# Schematic_CNC.net
KiCad netlist of a schematic drawn in Altium Designer
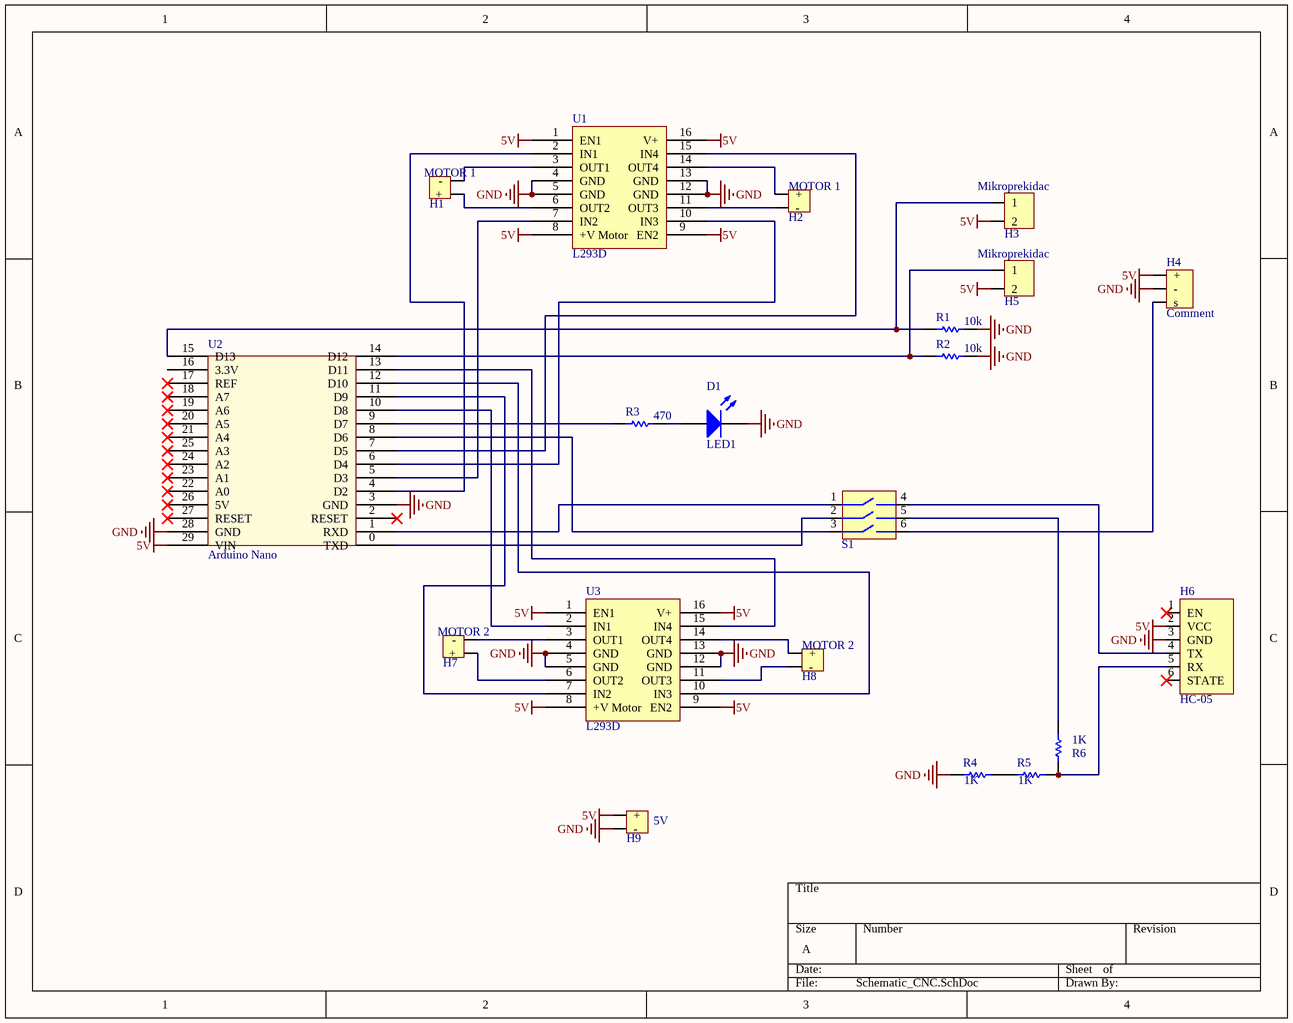
[diagram p0: Schematic_CNC.SchDoc]

(export (version "E")
  (design (tool "Eeschema 10.0.6"))
  (components
    (comp (ref "D1")
      (value "LED1")
      (footprint "LED-1")
      (description "Typical RED GaAs LED")
      (fields (field (name "PUBLISHER") "Altium Limited"))
      (libsource (lib "Miscellaneous Devices") (part "LED1"))
    )
    (comp (ref "H1")
      (value "MOTOR 1")
      (footprint "1x2 plavi sraf")
      (libsource (lib "Konektori") (part "1x2 plavi sraf"))
    )
    (comp (ref "H2")
      (value "MOTOR 1")
      (footprint "1x2 plavi sraf")
      (libsource (lib "") (part "1x2 plavi sraf_1"))
    )
    (comp (ref "H3")
      (value "Mikroprekidac")
      (footprint "1X2 HEADER")
      (libsource (lib "Konektori") (part "1X2 HEADER"))
    )
    (comp (ref "H4")
      (value "Comment")
      (footprint "1x3 plavi sraf")
      (libsource (lib "Konektori") (part "1x3 plavi sraf"))
    )
    (comp (ref "H5")
      (value "Mikroprekidac")
      (footprint "1X2 HEADER")
      (libsource (lib "Konektori") (part "1X2 HEADER"))
    )
    (comp (ref "H6") (value "HC-05") (footprint "HC-05") (libsource (lib "Bluetooth") (part "HC-05")))
    (comp (ref "H7")
      (value "MOTOR 2")
      (footprint "1x2 plavi sraf")
      (libsource (lib "Konektori") (part "1x2 plavi sraf"))
    )
    (comp (ref "H8")
      (value "MOTOR 2")
      (footprint "1x2 plavi sraf")
      (libsource (lib "") (part "1x2 plavi sraf_1"))
    )
    (comp (ref "H9") (value "5V") (footprint "1x2 plavi sraf") (libsource (lib "") (part "1x2 plavi sraf_1")))
    (comp (ref "R1")
      (value "10k")
      (footprint "AXIAL-0.3")
      (description "Resistor")
      (fields (field (name "Comment") "Res1") (field (name "PUBLISHER") "Altium Limited"))
      (libsource (lib "Miscellaneous Devices") (part "Res1"))
    )
    (comp (ref "R2")
      (value "10k")
      (footprint "AXIAL-0.3")
      (description "Resistor")
      (fields (field (name "Comment") "Res1") (field (name "PUBLISHER") "Altium Limited"))
      (libsource (lib "Miscellaneous Devices") (part "Res1"))
    )
    (comp (ref "R3")
      (value "470")
      (footprint "AXIAL-0.3")
      (description "Resistor")
      (fields (field (name "Comment") "Res1") (field (name "PUBLISHER") "Altium Limited"))
      (libsource (lib "Miscellaneous Devices") (part "Res1"))
    )
    (comp (ref "R4")
      (value "1K")
      (footprint "AXIAL-0.3")
      (description "Resistor")
      (fields (field (name "Comment") "Res1") (field (name "PUBLISHER") "Altium Limited"))
      (libsource (lib "Miscellaneous Devices") (part "Res1"))
    )
    (comp (ref "R5")
      (value "1K")
      (footprint "AXIAL-0.3")
      (description "Resistor")
      (fields (field (name "Comment") "Res1") (field (name "PUBLISHER") "Altium Limited"))
      (libsource (lib "Miscellaneous Devices") (part "Res1"))
    )
    (comp (ref "R6")
      (value "1K")
      (footprint "AXIAL-0.3")
      (description "Resistor")
      (fields (field (name "Comment") "Res1") (field (name "PUBLISHER") "Altium Limited"))
      (libsource (lib "Miscellaneous Devices") (part "Res1"))
    )
    (comp (ref "S1")
      (value "3X DIP Switch")
      (footprint "3X DIP SWITCH")
      (libsource (lib "Konektori") (part "3X DIP Switch"))
    )
    (comp (ref "U1")
      (value "L293D")
      (footprint "L293D")
      (description "Motor Driver")
      (libsource (lib "Motor Drivers") (part "L293D"))
    )
    (comp (ref "U2")
      (value "Arduino Nano")
      (footprint "Arduino nano")
      (libsource (lib "Arduino") (part "ArduinoNano"))
    )
    (comp (ref "U3")
      (value "L293D")
      (footprint "L293D")
      (description "Motor Driver")
      (libsource (lib "Motor Drivers") (part "L293D"))
    )
  )
  (nets
    (net (code "1") (name "5V") (class "Default")
      (node (ref "H3") (pin "2") (pinfunction "2_2") (pintype "passive"))
      (node (ref "H4") (pin "1") (pinfunction "+_1") (pintype "passive"))
      (node (ref "H5") (pin "2") (pinfunction "2_2") (pintype "passive"))
      (node (ref "H6") (pin "2") (pinfunction "VCC_2") (pintype "passive"))
      (node (ref "H9") (pin "1") (pinfunction "+_1") (pintype "passive"))
      (node (ref "U1") (pin "1") (pinfunction "EN1_1") (pintype "passive"))
      (node (ref "U1") (pin "16") (pinfunction "V+_16") (pintype "passive"))
      (node (ref "U1") (pin "8") (pinfunction "+V_Motor_8") (pintype "passive"))
      (node (ref "U1") (pin "9") (pinfunction "EN2_9") (pintype "passive"))
      (node (ref "U2") (pin "29") (pinfunction "VIN_29") (pintype "passive"))
      (node (ref "U3") (pin "1") (pinfunction "EN1_1") (pintype "passive"))
      (node (ref "U3") (pin "16") (pinfunction "V+_16") (pintype "passive"))
      (node (ref "U3") (pin "8") (pinfunction "+V_Motor_8") (pintype "passive"))
      (node (ref "U3") (pin "9") (pinfunction "EN2_9") (pintype "passive"))
    )
    (net (code "2") (name "GND") (class "Default")
      (node (ref "D1") (pin "2") (pinfunction "K_2") (pintype "passive"))
      (node (ref "H4") (pin "2") (pinfunction "-_2") (pintype "passive"))
      (node (ref "H6") (pin "3") (pinfunction "GND_3") (pintype "passive"))
      (node (ref "H9") (pin "2") (pinfunction "-_2") (pintype "passive"))
      (node (ref "R1") (pin "2") (pinfunction "2_2") (pintype "passive"))
      (node (ref "R2") (pin "2") (pinfunction "2_2") (pintype "passive"))
      (node (ref "R4") (pin "1") (pinfunction "1_1") (pintype "passive"))
      (node (ref "U1") (pin "12") (pinfunction "GND_12") (pintype "passive"))
      (node (ref "U1") (pin "13") (pinfunction "GND_13") (pintype "passive"))
      (node (ref "U1") (pin "4") (pinfunction "GND_4") (pintype "passive"))
      (node (ref "U1") (pin "5") (pinfunction "GND_5") (pintype "passive"))
      (node (ref "U2") (pin "28") (pinfunction "GND_28") (pintype "passive"))
      (node (ref "U2") (pin "3") (pinfunction "GND_3") (pintype "passive"))
      (node (ref "U3") (pin "12") (pinfunction "GND_12") (pintype "passive"))
      (node (ref "U3") (pin "13") (pinfunction "GND_13") (pintype "passive"))
      (node (ref "U3") (pin "4") (pinfunction "GND_4") (pintype "passive"))
      (node (ref "U3") (pin "5") (pinfunction "GND_5") (pintype "passive"))
    )
    (net (code "3") (name "Net-(D1-A)") (class "Default")
      (node (ref "D1") (pin "1") (pinfunction "A_1") (pintype "passive"))
      (node (ref "R3") (pin "2") (pinfunction "2_2") (pintype "passive"))
    )
    (net (code "4") (name "Net-(H1-+)") (class "Default")
      (node (ref "H1") (pin "1") (pinfunction "+_1") (pintype "passive"))
      (node (ref "U1") (pin "6") (pinfunction "OUT2_6") (pintype "passive"))
    )
    (net (code "5") (name "Net-(H1--)") (class "Default")
      (node (ref "H1") (pin "2") (pinfunction "-_2") (pintype "passive"))
      (node (ref "U1") (pin "3") (pinfunction "OUT1_3") (pintype "passive"))
    )
    (net (code "6") (name "Net-(H2-+)") (class "Default")
      (node (ref "H2") (pin "1") (pinfunction "+_1") (pintype "passive"))
      (node (ref "U1") (pin "14") (pinfunction "OUT4_14") (pintype "passive"))
    )
    (net (code "7") (name "Net-(H2--)") (class "Default")
      (node (ref "H2") (pin "2") (pinfunction "-_2") (pintype "passive"))
      (node (ref "U1") (pin "11") (pinfunction "OUT3_11") (pintype "passive"))
    )
    (net (code "8") (name "Net-(H4-s)") (class "Default")
      (node (ref "H4") (pin "3") (pinfunction "s_3") (pintype "passive"))
      (node (ref "S1") (pin "6") (pinfunction "6_6") (pintype "passive"))
    )
    (net (code "9") (name "Net-(H6-RX)") (class "Default")
      (node (ref "H6") (pin "5") (pinfunction "RX_5") (pintype "passive"))
      (node (ref "R5") (pin "2") (pinfunction "2_2") (pintype "passive"))
      (node (ref "R6") (pin "2") (pinfunction "2_2") (pintype "passive"))
    )
    (net (code "10") (name "Net-(H6-TX)") (class "Default")
      (node (ref "H6") (pin "4") (pinfunction "TX_4") (pintype "passive"))
      (node (ref "S1") (pin "4") (pinfunction "4_4") (pintype "passive"))
    )
    (net (code "11") (name "Net-(H7-+)") (class "Default")
      (node (ref "H7") (pin "1") (pinfunction "+_1") (pintype "passive"))
      (node (ref "U3") (pin "6") (pinfunction "OUT2_6") (pintype "passive"))
    )
    (net (code "12") (name "Net-(H7--)") (class "Default")
      (node (ref "H7") (pin "2") (pinfunction "-_2") (pintype "passive"))
      (node (ref "U3") (pin "3") (pinfunction "OUT1_3") (pintype "passive"))
    )
    (net (code "13") (name "Net-(H8-+)") (class "Default")
      (node (ref "H8") (pin "1") (pinfunction "+_1") (pintype "passive"))
      (node (ref "U3") (pin "14") (pinfunction "OUT4_14") (pintype "passive"))
    )
    (net (code "14") (name "Net-(H8--)") (class "Default")
      (node (ref "H8") (pin "2") (pinfunction "-_2") (pintype "passive"))
      (node (ref "U3") (pin "11") (pinfunction "OUT3_11") (pintype "passive"))
    )
    (net (code "15") (name "Net-(R4-Pad2)") (class "Default")
      (node (ref "R4") (pin "2") (pinfunction "2_2") (pintype "passive"))
      (node (ref "R5") (pin "1") (pinfunction "1_1") (pintype "passive"))
    )
    (net (code "16") (name "Net-(R6-Pad1)") (class "Default")
      (node (ref "R6") (pin "1") (pinfunction "1_1") (pintype "passive"))
      (node (ref "S1") (pin "5") (pinfunction "5_5") (pintype "passive"))
    )
    (net (code "17") (name "Net-(U1-IN1)") (class "Default")
      (node (ref "U1") (pin "2") (pinfunction "IN1_2") (pintype "passive"))
      (node (ref "U2") (pin "4") (pinfunction "D2_4") (pintype "passive"))
    )
    (net (code "18") (name "Net-(U1-IN2)") (class "Default")
      (node (ref "U1") (pin "7") (pinfunction "IN2_7") (pintype "passive"))
      (node (ref "U2") (pin "5") (pinfunction "D3_5") (pintype "passive"))
    )
    (net (code "19") (name "Net-(U1-IN3)") (class "Default")
      (node (ref "U1") (pin "10") (pinfunction "IN3_10") (pintype "passive"))
      (node (ref "U2") (pin "6") (pinfunction "D4_6") (pintype "passive"))
    )
    (net (code "20") (name "Net-(U1-IN4)") (class "Default")
      (node (ref "U1") (pin "15") (pinfunction "IN4_15") (pintype "passive"))
      (node (ref "U2") (pin "7") (pinfunction "D5_7") (pintype "passive"))
    )
    (net (code "21") (name "Net-(U2-D6)") (class "Default")
      (node (ref "S1") (pin "3") (pinfunction "3_3") (pintype "passive"))
      (node (ref "U2") (pin "8") (pinfunction "D6_8") (pintype "passive"))
    )
    (net (code "22") (name "Net-(U2-D7)") (class "Default")
      (node (ref "R3") (pin "1") (pinfunction "1_1") (pintype "passive"))
      (node (ref "U2") (pin "9") (pinfunction "D7_9") (pintype "passive"))
    )
    (net (code "23") (name "Net-(U2-D8)") (class "Default")
      (node (ref "U2") (pin "10") (pinfunction "D8_10") (pintype "passive"))
      (node (ref "U3") (pin "2") (pinfunction "IN1_2") (pintype "passive"))
    )
    (net (code "24") (name "Net-(U2-D9)") (class "Default")
      (node (ref "U2") (pin "11") (pinfunction "D9_11") (pintype "passive"))
      (node (ref "U3") (pin "7") (pinfunction "IN2_7") (pintype "passive"))
    )
    (net (code "25") (name "Net-(U2-D10)") (class "Default")
      (node (ref "U2") (pin "12") (pinfunction "D10_12") (pintype "passive"))
      (node (ref "U3") (pin "10") (pinfunction "IN3_10") (pintype "passive"))
    )
    (net (code "26") (name "Net-(U2-D11)") (class "Default")
      (node (ref "U2") (pin "13") (pinfunction "D11_13") (pintype "passive"))
      (node (ref "U3") (pin "15") (pinfunction "IN4_15") (pintype "passive"))
    )
    (net (code "27") (name "Net-(U2-D12)") (class "Default")
      (node (ref "H5") (pin "1") (pinfunction "1_1") (pintype "passive"))
      (node (ref "R2") (pin "1") (pinfunction "1_1") (pintype "passive"))
      (node (ref "U2") (pin "14") (pinfunction "D12_14") (pintype "passive"))
    )
    (net (code "28") (name "Net-(U2-D13)") (class "Default")
      (node (ref "H3") (pin "1") (pinfunction "1_1") (pintype "passive"))
      (node (ref "R1") (pin "1") (pinfunction "1_1") (pintype "passive"))
      (node (ref "U2") (pin "15") (pinfunction "D13_15") (pintype "passive"))
    )
    (net (code "29") (name "Net-(U2-RXD)") (class "Default")
      (node (ref "S1") (pin "1") (pinfunction "1_1") (pintype "passive"))
      (node (ref "U2") (pin "1") (pinfunction "RXD_1") (pintype "passive"))
    )
    (net (code "30") (name "Net-(U2-TXD)") (class "Default")
      (node (ref "S1") (pin "2") (pinfunction "2_2") (pintype "passive"))
      (node (ref "U2") (pin "0") (pinfunction "TXD_0") (pintype "passive"))
    )
    (net (code "31") (name "unconnected-(H6-EN-Pad1)") (class "Default")
      (node (ref "H6") (pin "1") (pinfunction "EN_1") (pintype "passive+no_connect"))
    )
    (net (code "32") (name "unconnected-(H6-STATE-Pad6)") (class "Default")
      (node (ref "H6") (pin "6") (pinfunction "STATE_6") (pintype "passive+no_connect"))
    )
    (net (code "33") (name "unconnected-(U2-3.3V-Pad16)") (class "Default")
      (node (ref "U2") (pin "16") (pinfunction "3.3V_16") (pintype "passive"))
    )
    (net (code "34") (name "unconnected-(U2-5V-Pad26)") (class "Default")
      (node (ref "U2") (pin "26") (pinfunction "5V_26") (pintype "passive+no_connect"))
    )
    (net (code "35") (name "unconnected-(U2-A0-Pad22)") (class "Default")
      (node (ref "U2") (pin "22") (pinfunction "A0_22") (pintype "passive+no_connect"))
    )
    (net (code "36") (name "unconnected-(U2-A1-Pad23)") (class "Default")
      (node (ref "U2") (pin "23") (pinfunction "A1_23") (pintype "passive+no_connect"))
    )
    (net (code "37") (name "unconnected-(U2-A2-Pad24)") (class "Default")
      (node (ref "U2") (pin "24") (pinfunction "A2_24") (pintype "passive+no_connect"))
    )
    (net (code "38") (name "unconnected-(U2-A3-Pad25)") (class "Default")
      (node (ref "U2") (pin "25") (pinfunction "A3_25") (pintype "passive+no_connect"))
    )
    (net (code "39") (name "unconnected-(U2-A4-Pad21)") (class "Default")
      (node (ref "U2") (pin "21") (pinfunction "A4_21") (pintype "passive+no_connect"))
    )
    (net (code "40") (name "unconnected-(U2-A5-Pad20)") (class "Default")
      (node (ref "U2") (pin "20") (pinfunction "A5_20") (pintype "passive+no_connect"))
    )
    (net (code "41") (name "unconnected-(U2-A6-Pad19)") (class "Default")
      (node (ref "U2") (pin "19") (pinfunction "A6_19") (pintype "passive+no_connect"))
    )
    (net (code "42") (name "unconnected-(U2-A7-Pad18)") (class "Default")
      (node (ref "U2") (pin "18") (pinfunction "A7_18") (pintype "passive+no_connect"))
    )
    (net (code "43") (name "unconnected-(U2-REF-Pad17)") (class "Default")
      (node (ref "U2") (pin "17") (pinfunction "REF_17") (pintype "passive+no_connect"))
    )
    (net (code "44") (name "unconnected-(U2-RESET-Pad2)") (class "Default")
      (node (ref "U2") (pin "2") (pinfunction "RESET_2") (pintype "passive+no_connect"))
    )
    (net (code "45") (name "unconnected-(U2-RESET-Pad27)") (class "Default")
      (node (ref "U2") (pin "27") (pinfunction "RESET_27") (pintype "passive+no_connect"))
    )
  )
)
